# Wacky_Racer_Schematic.net
KiCad netlist of a schematic drawn in Altium Designer
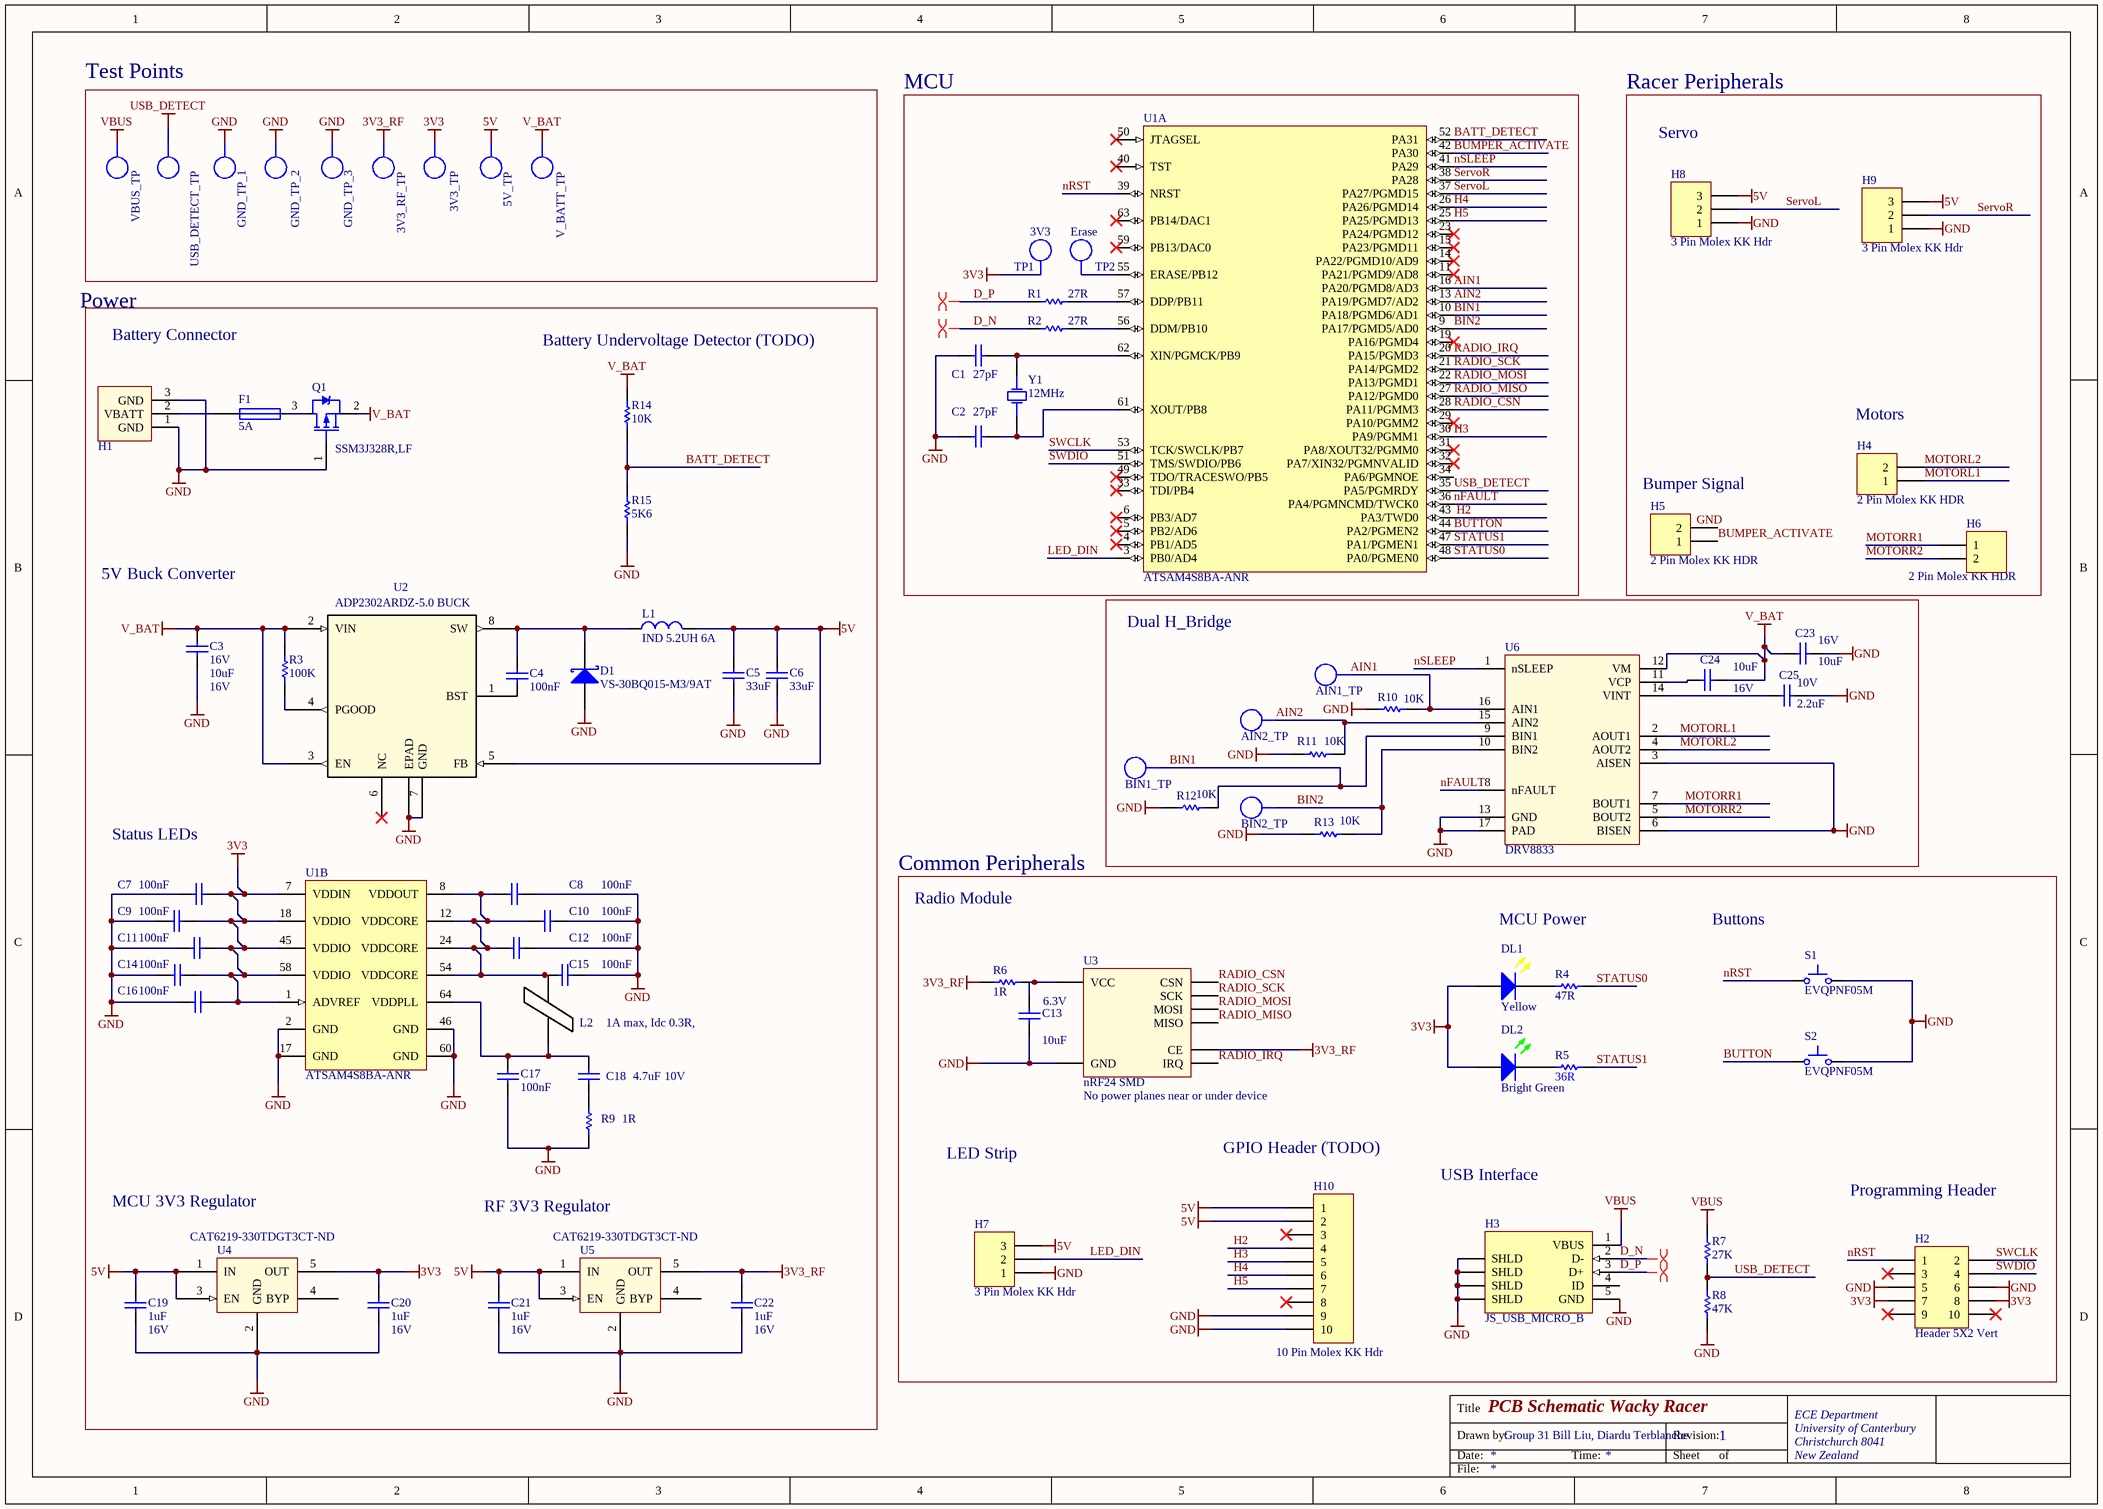
[diagram p0: Wacky Racer Schematic.schdoc]

(export (version "E")
  (design (tool "Eeschema 10.0.6"))
  (components
    (comp (ref "3V3_RF_TP")
      (value "TP")
      (footprint "TP_1206")
      (description "Test-Point 3.3x1.6x2.1mm SMD")
      (fields
        (field (name "MANUFACTURER") "Harwin Inc")
        (field (name "MANUFACTURER PART NUMBER") "S1751-46R")
      )
      (libsource (lib "ECE AD19Components_19V1") (part "TP_1206"))
    )
    (comp (ref "3V3_TP")
      (value "TP")
      (footprint "TP_1206")
      (description "Test-Point 3.3x1.6x2.1mm SMD")
      (fields
        (field (name "MANUFACTURER") "Harwin Inc")
        (field (name "MANUFACTURER PART NUMBER") "S1751-46R")
      )
      (libsource (lib "ECE AD19Components_19V1") (part "TP_1206"))
    )
    (comp (ref "5V_TP")
      (value "TP")
      (footprint "TP_1206")
      (description "Test-Point 3.3x1.6x2.1mm SMD")
      (fields
        (field (name "MANUFACTURER") "Harwin Inc")
        (field (name "MANUFACTURER PART NUMBER") "S1751-46R")
      )
      (libsource (lib "ECE AD19Components_19V1") (part "TP_1206"))
    )
    (comp (ref "AIN1_TP")
      (value "TP")
      (footprint "TP_1206")
      (description "Test-Point 3.3x1.6x2.1mm SMD")
      (fields
        (field (name "MANUFACTURER") "Harwin Inc")
        (field (name "MANUFACTURER PART NUMBER") "S1751-46R")
      )
      (libsource (lib "ECE AD19Components_19V1") (part "TP_1206"))
    )
    (comp (ref "AIN2_TP")
      (value "TP")
      (footprint "TP_1206")
      (description "Test-Point 3.3x1.6x2.1mm SMD")
      (fields
        (field (name "MANUFACTURER") "Harwin Inc")
        (field (name "MANUFACTURER PART NUMBER") "S1751-46R")
      )
      (libsource (lib "ECE AD19Components_19V1") (part "TP_1206"))
    )
    (comp (ref "BIN1_TP")
      (value "TP")
      (footprint "TP_1206")
      (description "Test-Point 3.3x1.6x2.1mm SMD")
      (fields
        (field (name "MANUFACTURER") "Harwin Inc")
        (field (name "MANUFACTURER PART NUMBER") "S1751-46R")
      )
      (libsource (lib "ECE AD19Components_19V1") (part "TP_1206"))
    )
    (comp (ref "BIN2_TP")
      (value "TP")
      (footprint "TP_1206")
      (description "Test-Point 3.3x1.6x2.1mm SMD")
      (fields
        (field (name "MANUFACTURER") "Harwin Inc")
        (field (name "MANUFACTURER PART NUMBER") "S1751-46R")
      )
      (libsource (lib "ECE AD19Components_19V1") (part "TP_1206"))
    )
    (comp (ref "C1")
      (value "27pF")
      (footprint "CAPC1608L")
      (description "CAP CER 27pF NPO/COG +-5% 50V 0603")
      (libsource (lib "ECE AD19Components_19V1") (part "CC_27pF_0603"))
    )
    (comp (ref "C2")
      (value "27pF")
      (footprint "CAPC1608L")
      (description "CAP CER 27pF NPO/COG +-5% 50V 0603")
      (libsource (lib "ECE AD19Components_19V1") (part "CC_27pF_0603"))
    )
    (comp (ref "C3")
      (value "10uF")
      (footprint "CAPC2012L")
      (description "CAP CER 10uF X5R 16V 0805")
      (fields
        (field (name "MANUFACTURER") "Samsung Electro-Mechanics")
        (field (name "MANUFACTURER PART NUMBER") "CL21A106KOQNNWE")
        (field (name "VOLTAGE - RATED") "16V")
        (field (name "MAX VOLTAGE") "16V")
      )
      (libsource (lib "ENCE461AD19_19V2") (part "CC_10uF_16V_0805"))
    )
    (comp (ref "C4")
      (value "100nF")
      (footprint "CAPC1608L")
      (description "CAP CER 100nF X7R +-10% 50V 0603")
      (libsource (lib "ECE AD19Components_19V1") (part "CC_100nF_0603"))
    )
    (comp (ref "C5")
      (value "33uF")
      (footprint "CAPC2012L")
      (description "CAP CER 33uF X5R 6V3 0805")
      (fields
        (field (name "MANUFACTURER") "TDK Corporation")
        (field (name "MANUFACTURER PART NUMBER") "C2012X5R0J336M125AC")
      )
      (libsource (lib "ENCE461AD19_19V2") (part "CC_33uF_6V3_0805"))
    )
    (comp (ref "C6")
      (value "33uF")
      (footprint "CAPC2012L")
      (description "CAP CER 33uF X5R 6V3 0805")
      (fields
        (field (name "MANUFACTURER") "TDK Corporation")
        (field (name "MANUFACTURER PART NUMBER") "C2012X5R0J336M125AC")
      )
      (libsource (lib "ENCE461AD19_19V2") (part "CC_33uF_6V3_0805"))
    )
    (comp (ref "C7")
      (value "100nF")
      (footprint "CAPC1608L")
      (description "CAP CER 100nF X7R +-10% 50V 0603")
      (libsource (lib "ECE AD19Components_19V1") (part "CC_100nF_0603"))
    )
    (comp (ref "C8")
      (value "100nF")
      (footprint "CAPC1608L")
      (description "CAP CER 100nF X7R +-10% 50V 0603")
      (libsource (lib "ECE AD19Components_19V1") (part "CC_100nF_0603"))
    )
    (comp (ref "C9")
      (value "100nF")
      (footprint "CAPC1608L")
      (description "CAP CER 100nF X7R +-10% 50V 0603")
      (libsource (lib "ECE AD19Components_19V1") (part "CC_100nF_0603"))
    )
    (comp (ref "C10")
      (value "100nF")
      (footprint "CAPC1608L")
      (description "CAP CER 100nF X7R +-10% 50V 0603")
      (libsource (lib "ECE AD19Components_19V1") (part "CC_100nF_0603"))
    )
    (comp (ref "C11")
      (value "100nF")
      (footprint "CAPC1608L")
      (description "CAP CER 100nF X7R +-10% 50V 0603")
      (libsource (lib "ECE AD19Components_19V1") (part "CC_100nF_0603"))
    )
    (comp (ref "C12")
      (value "100nF")
      (footprint "CAPC1608L")
      (description "CAP CER 100nF X7R +-10% 50V 0603")
      (libsource (lib "ECE AD19Components_19V1") (part "CC_100nF_0603"))
    )
    (comp (ref "C13")
      (value "10uF")
      (footprint "CAPC1608L")
      (description "CAP CER 10UF X5R +-20% 6V3 0603")
      (fields (field (name "VOLTAGE - RATED") "6.3V"))
      (libsource (lib "ECE AD19Components_19V1") (part "CC_10uF_0603"))
    )
    (comp (ref "C14")
      (value "100nF")
      (footprint "CAPC1608L")
      (description "CAP CER 100nF X7R +-10% 50V 0603")
      (libsource (lib "ECE AD19Components_19V1") (part "CC_100nF_0603"))
    )
    (comp (ref "C15")
      (value "100nF")
      (footprint "CAPC1608L")
      (description "CAP CER 100nF X7R +-10% 50V 0603")
      (libsource (lib "ECE AD19Components_19V1") (part "CC_100nF_0603"))
    )
    (comp (ref "C16")
      (value "100nF")
      (footprint "CAPC1608L")
      (description "CAP CER 100nF X7R +-10% 50V 0603")
      (libsource (lib "ECE AD19Components_19V1") (part "CC_100nF_0603"))
    )
    (comp (ref "C17")
      (value "100nF")
      (footprint "CAPC1608L")
      (description "CAP CER 100nF X7R +-10% 50V 0603")
      (libsource (lib "ECE AD19Components_19V1") (part "CC_100nF_0603"))
    )
    (comp (ref "C18")
      (value "4.7uF")
      (footprint "CAPC1608N")
      (description "CAP CER 4.7uF X5R +-20%  10V 0603")
      (fields (field (name "MAX VOLTAGE") "10V"))
      (libsource (lib "ECE AD19Components_19V1") (part "CC_4.7uF_0603"))
    )
    (comp (ref "C19")
      (value "1uF")
      (footprint "CAPC1608L")
      (description "CAP CER 1uF Y5V -20% +80% 16V 0603")
      (fields (field (name "MAX VOLTAGE") "16V"))
      (libsource (lib "ECE AD19Components_19V1") (part "CC_1uF_0603"))
    )
    (comp (ref "C20")
      (value "1uF")
      (footprint "CAPC1608L")
      (description "CAP CER 1uF Y5V -20% +80% 16V 0603")
      (fields (field (name "MAX VOLTAGE") "16V"))
      (libsource (lib "ECE AD19Components_19V1") (part "CC_1uF_0603"))
    )
    (comp (ref "C21")
      (value "1uF")
      (footprint "CAPC1608L")
      (description "CAP CER 1uF Y5V -20% +80% 16V 0603")
      (fields (field (name "MAX VOLTAGE") "16V"))
      (libsource (lib "ECE AD19Components_19V1") (part "CC_1uF_0603"))
    )
    (comp (ref "C22")
      (value "1uF")
      (footprint "CAPC1608L")
      (description "CAP CER 1uF Y5V -20% +80% 16V 0603")
      (fields (field (name "MAX VOLTAGE") "16V"))
      (libsource (lib "ECE AD19Components_19V1") (part "CC_1uF_0603"))
    )
    (comp (ref "C23")
      (value "10uF")
      (footprint "CAPC2012L")
      (description "CAP CER 10uF X5R 16V 0805")
      (fields
        (field (name "MANUFACTURER") "Samsung Electro-Mechanics")
        (field (name "MANUFACTURER PART NUMBER") "CL21A106KOQNNWE")
        (field (name "VOLTAGE - RATED") "16V")
      )
      (libsource (lib "ENCE461AD19_19V2") (part "CC_10uF_16V_0805"))
    )
    (comp (ref "C24")
      (value "10uF")
      (footprint "CAPC2012L")
      (description "CAP CER 10uF X5R 16V 0805")
      (fields
        (field (name "MANUFACTURER") "Samsung Electro-Mechanics")
        (field (name "MANUFACTURER PART NUMBER") "CL21A106KOQNNWE")
        (field (name "VOLTAGE - RATED") "16V")
      )
      (libsource (lib "ENCE461AD19_19V2") (part "CC_10uF_16V_0805"))
    )
    (comp (ref "C25")
      (value "2.2uF")
      (footprint "CAPC1608L")
      (description "CAP CER 2.2uF X5R +-20% 10V 0603")
      (fields (field (name "MAX VOLTAGE") "10V"))
      (libsource (lib "ECE AD19Components_19V1") (part "CC_2.2uF_0603"))
    )
    (comp (ref "D1")
      (value "VS-30BQ015-M3/9AT")
      (footprint "SMC")
      (description "DIODE, SCHOTTKY, 3A, 15V, DO-214AB / SMC")
      (fields (field (name "MANUFACTURER") "Vishay Semiconductors"))
      (libsource (lib "ECE AD19Components_19V1") (part "DS_VS-30BQ015-M3"))
    )
    (comp (ref "DL1")
      (value "Yellow")
      (footprint "WL-SMCW0603")
      (description "LED Yellow 120mcd 0603 SMD")
      (fields
        (field (name "MANUFACTURER") "WURTH ELEKTRONIK")
        (field (name "MANUFACTURER PART NUMBER") "150060YS75000")
        (field (name "LED COLOUR") "Yellow")
      )
      (libsource (lib "ECE AD19Components_19V1") (part "DL_150060YS75000"))
    )
    (comp (ref "DL2")
      (value "Bright Green")
      (footprint "WL-SMCW0603")
      (description "LED Bright Green 40mcd 0603 SMD")
      (fields
        (field (name "MANUFACTURER") "WURTH ELEKTRONIK")
        (field (name "MANUFACTURER PART NUMBER") "150060VS75000")
        (field (name "LED COLOUR") "Bright Green")
      )
      (libsource (lib "ECE AD19Components_19V1") (part "DL_150060VS75000"))
    )
    (comp (ref "F1")
      (value "5A")
      (footprint "RESC3216N")
      (description "Fuse 5.0A Fast Acting 1206 SMD")
      (fields (field (name "MANUFACTURER PART NUMBER") "C1F5") (field (name "MANUFACTURER") "Bel TRP"))
      (libsource (lib "ECE AD19Components_19V1") (part "FS_Fuse_5.0A"))
    )
    (comp (ref "GND_TP_1")
      (value "TP")
      (footprint "TP_1206")
      (description "Test-Point 3.3x1.6x2.1mm SMD")
      (fields
        (field (name "MANUFACTURER") "Harwin Inc")
        (field (name "MANUFACTURER PART NUMBER") "S1751-46R")
      )
      (libsource (lib "ECE AD19Components_19V1") (part "TP_1206"))
    )
    (comp (ref "GND_TP_2")
      (value "TP")
      (footprint "TP_1206")
      (description "Test-Point 3.3x1.6x2.1mm SMD")
      (fields
        (field (name "MANUFACTURER") "Harwin Inc")
        (field (name "MANUFACTURER PART NUMBER") "S1751-46R")
      )
      (libsource (lib "ECE AD19Components_19V1") (part "TP_1206"))
    )
    (comp (ref "GND_TP_3")
      (value "TP")
      (footprint "TP_1206")
      (description "Test-Point 3.3x1.6x2.1mm SMD")
      (fields
        (field (name "MANUFACTURER") "Harwin Inc")
        (field (name "MANUFACTURER PART NUMBER") "S1751-46R")
      )
      (libsource (lib "ECE AD19Components_19V1") (part "TP_1206"))
    )
    (comp (ref "H1")
      (value "Battery_HEADER_3pin")
      (footprint "BATT_HEADER_3POS")
      (description "3Pin Header 2.54mm spacing")
      (libsource (lib "ENCE461AD19_19V2") (part "Battery_HEADER_3pin"))
    )
    (comp (ref "H2")
      (value "Header 5X2 Vert")
      (footprint "IDC2.54-V10D")
      (description "IDC Header, 2,54mm, 10-Pin, Vert")
      (libsource (lib "ECE AD19Components_19V1") (part "JA_HDR_IDC_5X2_VERT"))
    )
    (comp (ref "H3")
      (value "JS_USB_MICRO_B")
      (footprint "FCI_USB_10118194-0001LF")
      (description "CONN USB MICRO B RECPT SMT R/A")
      (fields (field (name "MANUFACTURER") "FCI") (field (name "MANUFACTURER PART NUMBER") "10118194-0001LF"))
      (libsource (lib "ECE AD19Components_19V1") (part "JS_USB_MICRO_B_SMT"))
    )
    (comp (ref "H4")
      (value "2 Pin Molex KK HDR")
      (footprint "MOLEX_KK_2_HDR")
      (description "CONN HEADER 2POS 2.54mm VERT_Thru Hole")
      (libsource (lib "ECE AD19Components_19V1") (part "JA_MOLEX_KK_2POS"))
    )
    (comp (ref "H5")
      (value "2 Pin Molex KK HDR")
      (footprint "MOLEX_KK_2_HDR")
      (description "CONN HEADER 2POS 2.54mm VERT_Thru Hole")
      (libsource (lib "ECE AD19Components_19V1") (part "JA_MOLEX_KK_2POS"))
    )
    (comp (ref "H6")
      (value "2 Pin Molex KK HDR")
      (footprint "MOLEX_KK_2_HDR")
      (description "CONN HEADER 2POS 2.54mm VERT_Thru Hole")
      (libsource (lib "") (part "JA_MOLEX_KK_2POS_1"))
    )
    (comp (ref "H7")
      (value "3 Pin Molex KK Hdr")
      (footprint "MOLEX_KK_3_HDR")
      (description "CONN HEADER 3POS 2.54mm VERT_Thru Hole")
      (fields (field (name "MANUFACTURER") "Molex"))
      (libsource (lib "ECE AD19Components_19V1") (part "JA_MOLEX_KK_3POS"))
    )
    (comp (ref "H8")
      (value "3 Pin Molex KK Hdr")
      (footprint "MOLEX_KK_3_HDR")
      (description "CONN HEADER 3POS 2.54mm VERT_Thru Hole")
      (fields (field (name "MANUFACTURER") "Molex"))
      (libsource (lib "ECE AD19Components_19V1") (part "JA_MOLEX_KK_3POS"))
    )
    (comp (ref "H9")
      (value "3 Pin Molex KK Hdr")
      (footprint "MOLEX_KK_3_HDR")
      (description "CONN HEADER 3POS 2.54mm VERT_Thru Hole")
      (fields (field (name "MANUFACTURER") "Molex"))
      (libsource (lib "ECE AD19Components_19V1") (part "JA_MOLEX_KK_3POS"))
    )
    (comp (ref "H10")
      (value "10 Pin Molex KK Hdr")
      (footprint "MOLEX_KK_10_HDR")
      (description "CONN HEADER 10POS 2.54mm VERT_ Thru Hole")
      (libsource (lib "ECE AD19Components_19V1") (part "JA_MOLEX_KK_10POS"))
    )
    (comp (ref "L1")
      (value "IND 5.2UH 6A")
      (footprint "INDUCTOR5u2")
      (description "FIXED IND 5.2UH 6A 22 MOHM SMD")
      (fields
        (field (name "MANUFACTURER") "Sumida America Components Inc.")
        (field (name "MANUFACTURER PART NUMBER") "CDRH104RNP-5R2NC")
      )
      (libsource (lib "ENCE461AD19_19V2") (part "CDRH104RNP-5R2NC"))
    )
    (comp (ref "L2")
      (value "1A max, Idc 0.3R,")
      (footprint "INDC3216L")
      (description "Ferrite Bead, Rdc 0.3R, Z100MHZ 600R, Imax 1A, SMD 1206")
      (fields
        (field (name "MANUFACTURER") "FAIR-RITE")
        (field (name "MANUFACTURER PART NUMBER") "2512066017Y1")
      )
      (libsource (lib "ECE AD19Components_19V1") (part "IN_Ferrite-Bead"))
    )
    (comp (ref "Q1")
      (value "SSM3J328R,LF")
      (footprint "SOT23_L")
      (description "MOSFET P-CH 20V 6A SOT23-3")
      (fields
        (field (name "MANUFACTURER") "Toshiba")
        (field (name "MANUFACTURER PART NUMBER") "SSM3J328R,LF")
      )
      (libsource (lib "ECE AD19Components_19V1") (part "TM_SSM3J328R"))
    )
    (comp (ref "R1")
      (value "27R")
      (footprint "RESC1608L")
      (description "RES 27 OHM 1/10W 5% 0603 SMD")
      (libsource (lib "ECE AD19Components_19V1") (part "RS_27R"))
    )
    (comp (ref "R2")
      (value "27R")
      (footprint "RESC1608L")
      (description "RES 27 OHM 1/10W 5% 0603 SMD")
      (libsource (lib "ECE AD19Components_19V1") (part "RS_27R"))
    )
    (comp (ref "R3")
      (value "100K")
      (footprint "RESC1608L")
      (description "RES 100K OHM 1/10W 5% 0603 SMD")
      (libsource (lib "ECE AD19Components_19V1") (part "RS_100K"))
    )
    (comp (ref "R4")
      (value "47R")
      (footprint "RESC1608L")
      (description "RES 47 OHM 1/10W 5% 0603 SMD")
      (libsource (lib "ECE AD19Components_19V1") (part "RS_47R"))
    )
    (comp (ref "R5")
      (value "36R")
      (footprint "RESC1608L")
      (description "RES 36 OHM 1/10W 5% 0603 SMD")
      (libsource (lib "ECE AD19Components_19V1") (part "RS_36R"))
    )
    (comp (ref "R6")
      (value "1R")
      (footprint "RESC3216L")
      (description "RES 1R OHM 1/4W 5% 1206 SMD")
      (libsource (lib "ECE AD19Components_19V1") (part "RT_1R"))
    )
    (comp (ref "R7")
      (value "27K")
      (footprint "RESC1608L")
      (description "RES 27K OHM 1/10W 5% 0603 SMD")
      (libsource (lib "ECE AD19Components_19V1") (part "RS_27K"))
    )
    (comp (ref "R8")
      (value "47K")
      (footprint "RESC1608N")
      (description "RES 47.0K OHM 1/10W 5% 0603 SMD")
      (libsource (lib "ECE AD19Components_19V1") (part "RS_47K"))
    )
    (comp (ref "R9")
      (value "1R")
      (footprint "RESC3216L")
      (description "RES 1R OHM 1/4W 5% 1206 SMD")
      (libsource (lib "ECE AD19Components_19V1") (part "RT_1R"))
    )
    (comp (ref "R10")
      (value "10K")
      (footprint "RESC1608L")
      (description "RES 10.0K OHM 1/10W 5% 0603 SMD")
      (libsource (lib "ECE AD19Components_19V1") (part "RS_10K"))
    )
    (comp (ref "R11")
      (value "10K")
      (footprint "RESC1608L")
      (description "RES 10.0K OHM 1/10W 5% 0603 SMD")
      (libsource (lib "ECE AD19Components_19V1") (part "RS_10K"))
    )
    (comp (ref "R12")
      (value "10K")
      (footprint "RESC1608L")
      (description "RES 10.0K OHM 1/10W 5% 0603 SMD")
      (libsource (lib "ECE AD19Components_19V1") (part "RS_10K"))
    )
    (comp (ref "R13")
      (value "10K")
      (footprint "RESC1608L")
      (description "RES 10.0K OHM 1/10W 5% 0603 SMD")
      (libsource (lib "ECE AD19Components_19V1") (part "RS_10K"))
    )
    (comp (ref "R14")
      (value "10K")
      (footprint "RESC1608L")
      (description "RES 10.0K OHM 1/10W 5% 0603 SMD")
      (libsource (lib "ECE AD19Components_19V1") (part "RS_10K"))
    )
    (comp (ref "R15")
      (value "5K6")
      (footprint "RESC1608L")
      (description "RES 5.6K OHM 1/10W 5% 0603 SMD")
      (libsource (lib "ECE AD19Components_19V1") (part "RS_5K6"))
    )
    (comp (ref "S1")
      (value "EVQPNF05M")
      (footprint "EVQPNF05M")
      (description "Panasonic 6 x 3.5mm SMD Light Touch Switch Type SMD")
      (fields (field (name "MANUFACTURER") "Panasonic"))
      (libsource (lib "ECE AD19Components_19V1") (part "WS_EVQPNF05M"))
    )
    (comp (ref "S2")
      (value "EVQPNF05M")
      (footprint "EVQPNF05M")
      (description "Panasonic 6 x 3.5mm SMD Light Touch Switch Type SMD")
      (fields (field (name "MANUFACTURER") "Panasonic"))
      (libsource (lib "ECE AD19Components_19V1") (part "WS_EVQPNF05M"))
    )
    (comp (ref "TP1")
      (value "3V3")
      (footprint "TP_1206")
      (description "Test-Point 3.3x1.6x2.1mm SMD")
      (fields
        (field (name "MANUFACTURER") "Harwin Inc")
        (field (name "MANUFACTURER PART NUMBER") "S1751-46R")
      )
      (libsource (lib "ECE AD19Components_19V1") (part "TP_1206"))
    )
    (comp (ref "TP2")
      (value "Erase")
      (footprint "TP_1206")
      (description "Test-Point 3.3x1.6x2.1mm SMD")
      (fields
        (field (name "MANUFACTURER") "Harwin Inc")
        (field (name "MANUFACTURER PART NUMBER") "S1751-46R")
      )
      (libsource (lib "ECE AD19Components_19V1") (part "TP_1206"))
    )
    (comp (ref "U1")
      (value "ATSAM4S8BA-ANR")
      (footprint "LQFP64_L")
      (description "IC MCU 32BIT 512KB FLASH 64LQFP")
      (fields (field (name "MANUFACTURER") "Atmel"))
      (libsource (lib "ECE AD19Components_19V1") (part "SE_ATSAM4S16BA-MU"))
    )
    (comp (ref "U2")
      (value "ADP2302ARDZ-5.0 BUCK")
      (footprint "RD_8_1")
      (description "IC REG BUCK 5V 2A 8SOIC")
      (fields (field (name "MANUFACTURER_PART_NUMBER") "ADP2302ARDZ-5.0-R7"))
      (libsource (lib "ENCE461AD19_19V2") (part "ADP2302ARDZ-5.0-R7"))
    )
    (comp (ref "U3")
      (value "nRF24 SMD")
      (footprint "NRF24")
      (description "nRF24 SMD Module")
      (fields (field (name "WARNING") "No power planes near or under device"))
      (libsource (lib "ENCE461AD19_19V2") (part "NRF24"))
    )
    (comp (ref "U4")
      (value "CAT6219-330TDGT3")
      (footprint "SOT95P280X145-5N")
      (description "IC REG LIN 3.3V 500MA TSOT23-5")
      (fields
        (field (name "BASE PART NUMBER") "CAT6219")
        (field (name "SUPPLIER PART NUMBER") "CAT6219-330TDGT3CT-ND")
      )
      (libsource (lib "ENCE461AD19_19V2") (part "SV_CAT6219-330TDGT3"))
    )
    (comp (ref "U5")
      (value "CAT6219-330TDGT3")
      (footprint "SOT95P280X145-5N")
      (description "IC REG LIN 3.3V 500MA TSOT23-5")
      (fields
        (field (name "BASE PART NUMBER") "CAT6219")
        (field (name "SUPPLIER PART NUMBER") "CAT6219-330TDGT3CT-ND")
      )
      (libsource (lib "ENCE461AD19_19V2") (part "SV_CAT6219-330TDGT3"))
    )
    (comp (ref "U6")
      (value "DRV8833")
      (footprint "HTSOP16")
      (description "Dual H-Bridge Motor Driver 1.5A")
      (libsource (lib "ENCE461AD19_19V2") (part "DRV8833"))
    )
    (comp (ref "USB_DETECT_TP")
      (value "TP")
      (footprint "TP_1206")
      (description "Test-Point 3.3x1.6x2.1mm SMD")
      (fields
        (field (name "MANUFACTURER") "Harwin Inc")
        (field (name "MANUFACTURER PART NUMBER") "S1751-46R")
      )
      (libsource (lib "ECE AD19Components_19V1") (part "TP_1206"))
    )
    (comp (ref "VBUS_TP")
      (value "TP")
      (footprint "TP_1206")
      (description "Test-Point 3.3x1.6x2.1mm SMD")
      (fields
        (field (name "MANUFACTURER") "Harwin Inc")
        (field (name "MANUFACTURER PART NUMBER") "S1751-46R")
      )
      (libsource (lib "ECE AD19Components_19V1") (part "TP_1206"))
    )
    (comp (ref "V_BATT_TP")
      (value "TP")
      (footprint "TP_1206")
      (description "Test-Point 3.3x1.6x2.1mm SMD")
      (fields
        (field (name "MANUFACTURER") "Harwin Inc")
        (field (name "MANUFACTURER PART NUMBER") "S1751-46R")
      )
      (libsource (lib "ECE AD19Components_19V1") (part "TP_1206"))
    )
    (comp (ref "Y1")
      (value "12MHz")
      (footprint "6.0X3.5-4")
      (description "CRYSTAL 12MHZ 18PF 6X3.5mm SMD")
      (fields
        (field (name "MANUFACTURER") "CTS-Frequency Controls")
        (field (name "MANUFACTURER PART NUMBER") "406C35D12M00000")
        (field (name "FREQUENCY") "12MHz")
      )
      (libsource (lib "ECE AD19Components_19V1") (part "XT_CRYSTAL_12MHz_18pF"))
    )
  )
  (nets
    (net (code "1") (name "/AIN1") (class "Default")
      (node (ref "AIN1_TP") (pin "1") (pinfunction "1_1") (pintype "passive"))
      (node (ref "R10") (pin "2") (pinfunction "2_2") (pintype "passive"))
      (node (ref "U1") (pin "16") (pinfunction "PA20/PGMD8/AD3_16") (pintype "bidirectional"))
      (node (ref "U6") (pin "16") (pinfunction "AIN1_16") (pintype "passive"))
    )
    (net (code "2") (name "/AIN2") (class "Default")
      (node (ref "AIN2_TP") (pin "1") (pinfunction "1_1") (pintype "passive"))
      (node (ref "R11") (pin "2") (pinfunction "2_2") (pintype "passive"))
      (node (ref "U1") (pin "13") (pinfunction "PA19/PGMD7/AD2_13") (pintype "bidirectional"))
      (node (ref "U6") (pin "15") (pinfunction "AIN2_15") (pintype "passive"))
    )
    (net (code "3") (name "/BATT_DETECT") (class "Default")
      (node (ref "R14") (pin "1") (pinfunction "1_1") (pintype "passive"))
      (node (ref "R15") (pin "2") (pinfunction "2_2") (pintype "passive"))
      (node (ref "U1") (pin "52") (pinfunction "PA31_52") (pintype "bidirectional"))
    )
    (net (code "4") (name "/BIN1") (class "Default")
      (node (ref "BIN1_TP") (pin "1") (pinfunction "1_1") (pintype "passive"))
      (node (ref "R12") (pin "2") (pinfunction "2_2") (pintype "passive"))
      (node (ref "U1") (pin "10") (pinfunction "PA18/PGMD6/AD1_10") (pintype "bidirectional"))
      (node (ref "U6") (pin "9") (pinfunction "BIN1_9") (pintype "passive"))
    )
    (net (code "5") (name "/BIN2") (class "Default")
      (node (ref "BIN2_TP") (pin "1") (pinfunction "1_1") (pintype "passive"))
      (node (ref "R13") (pin "2") (pinfunction "2_2") (pintype "passive"))
      (node (ref "U1") (pin "9") (pinfunction "PA17/PGMD5/AD0_9") (pintype "bidirectional"))
      (node (ref "U6") (pin "10") (pinfunction "BIN2_10") (pintype "passive"))
    )
    (net (code "6") (name "/BUMPER_ACTIVATE") (class "Default")
      (node (ref "H5") (pin "1") (pinfunction "1_1") (pintype "passive"))
      (node (ref "U1") (pin "42") (pinfunction "PA30_42") (pintype "bidirectional"))
    )
    (net (code "7") (name "/BUTTON") (class "Default")
      (node (ref "S2") (pin "1") (pintype "passive"))
      (node (ref "U1") (pin "44") (pinfunction "PA2/PGMEN2_44") (pintype "bidirectional"))
    )
    (net (code "8") (name "/D_N") (class "Default")
      (node (ref "H3") (pin "2") (pinfunction "D-_2") (pintype "input"))
      (node (ref "R2") (pin "1") (pinfunction "1_1") (pintype "passive"))
    )
    (net (code "9") (name "/D_P") (class "Default")
      (node (ref "H3") (pin "3") (pinfunction "D+_3") (pintype "input"))
      (node (ref "R1") (pin "1") (pinfunction "1_1") (pintype "passive"))
    )
    (net (code "10") (name "/H2") (class "Default")
      (node (ref "H10") (pin "4") (pinfunction "4_4") (pintype "passive"))
      (node (ref "U1") (pin "43") (pinfunction "PA3/TWD0_43") (pintype "bidirectional"))
    )
    (net (code "11") (name "/H3") (class "Default")
      (node (ref "H10") (pin "5") (pinfunction "5_5") (pintype "passive"))
      (node (ref "U1") (pin "30") (pinfunction "PA9/PGMM1_30") (pintype "bidirectional"))
    )
    (net (code "12") (name "/H4") (class "Default")
      (node (ref "H10") (pin "6") (pinfunction "6_6") (pintype "passive"))
      (node (ref "U1") (pin "26") (pinfunction "PA26/PGMD14_26") (pintype "bidirectional"))
    )
    (net (code "13") (name "/H5") (class "Default")
      (node (ref "H10") (pin "7") (pinfunction "7_7") (pintype "passive"))
      (node (ref "U1") (pin "25") (pinfunction "PA25/PGMD13_25") (pintype "bidirectional"))
    )
    (net (code "14") (name "/LED_DIN") (class "Default")
      (node (ref "H7") (pin "2") (pinfunction "2_2") (pintype "passive"))
      (node (ref "U1") (pin "3") (pinfunction "PB0/AD4_3") (pintype "bidirectional"))
    )
    (net (code "15") (name "/MOTORL1") (class "Default")
      (node (ref "H4") (pin "1") (pinfunction "1_1") (pintype "passive"))
      (node (ref "U6") (pin "2") (pinfunction "AOUT1_2") (pintype "passive"))
    )
    (net (code "16") (name "/MOTORL2") (class "Default")
      (node (ref "H4") (pin "2") (pinfunction "2_2") (pintype "passive"))
      (node (ref "U6") (pin "4") (pinfunction "AOUT2_4") (pintype "passive"))
    )
    (net (code "17") (name "/MOTORR1") (class "Default")
      (node (ref "H6") (pin "1") (pinfunction "1_1") (pintype "passive"))
      (node (ref "U6") (pin "7") (pinfunction "BOUT1_7") (pintype "passive"))
    )
    (net (code "18") (name "/MOTORR2") (class "Default")
      (node (ref "H6") (pin "2") (pinfunction "2_2") (pintype "passive"))
      (node (ref "U6") (pin "5") (pinfunction "BOUT2_5") (pintype "passive"))
    )
    (net (code "19") (name "/RADIO_CSN") (class "Default")
      (node (ref "U1") (pin "28") (pinfunction "PA11/PGMM3_28") (pintype "bidirectional"))
      (node (ref "U3") (pin "4") (pinfunction "CSN_4") (pintype "passive"))
    )
    (net (code "20") (name "/RADIO_IRQ") (class "Default")
      (node (ref "U1") (pin "20") (pinfunction "PA15/PGMD3_20") (pintype "bidirectional"))
      (node (ref "U3") (pin "8") (pinfunction "IRQ_8") (pintype "passive"))
    )
    (net (code "21") (name "/RADIO_MISO") (class "Default")
      (node (ref "U1") (pin "27") (pinfunction "PA12/PGMD0_27") (pintype "bidirectional"))
      (node (ref "U3") (pin "7") (pinfunction "MISO_7") (pintype "passive"))
    )
    (net (code "22") (name "/RADIO_MOSI") (class "Default")
      (node (ref "U1") (pin "22") (pinfunction "PA13/PGMD1_22") (pintype "bidirectional"))
      (node (ref "U3") (pin "6") (pinfunction "MOSI_6") (pintype "passive"))
    )
    (net (code "23") (name "/RADIO_SCK") (class "Default")
      (node (ref "U1") (pin "21") (pinfunction "PA14/PGMD2_21") (pintype "bidirectional"))
      (node (ref "U3") (pin "5") (pinfunction "SCK_5") (pintype "passive"))
    )
    (net (code "24") (name "/STATUS0") (class "Default")
      (node (ref "R4") (pin "2") (pinfunction "2_2") (pintype "passive"))
      (node (ref "U1") (pin "48") (pinfunction "PA0/PGMEN0_48") (pintype "bidirectional"))
    )
    (net (code "25") (name "/STATUS1") (class "Default")
      (node (ref "R5") (pin "2") (pinfunction "2_2") (pintype "passive"))
      (node (ref "U1") (pin "47") (pinfunction "PA1/PGMEN1_47") (pintype "bidirectional"))
    )
    (net (code "26") (name "/SWCLK") (class "Default")
      (node (ref "H2") (pin "2") (pinfunction "2_2") (pintype "passive"))
      (node (ref "U1") (pin "53") (pinfunction "TCK/SWCLK/PB7_53") (pintype "bidirectional"))
    )
    (net (code "27") (name "/SWDIO") (class "Default")
      (node (ref "H2") (pin "4") (pinfunction "4_4") (pintype "passive"))
      (node (ref "U1") (pin "51") (pinfunction "TMS/SWDIO/PB6_51") (pintype "bidirectional"))
    )
    (net (code "28") (name "/ServoL") (class "Default")
      (node (ref "H8") (pin "2") (pinfunction "2_2") (pintype "passive"))
      (node (ref "U1") (pin "37") (pinfunction "PA27/PGMD15_37") (pintype "bidirectional"))
    )
    (net (code "29") (name "/ServoR") (class "Default")
      (node (ref "H9") (pin "2") (pinfunction "2_2") (pintype "passive"))
      (node (ref "U1") (pin "38") (pinfunction "PA28_38") (pintype "bidirectional"))
    )
    (net (code "30") (name "/nFAULT") (class "Default")
      (node (ref "U1") (pin "36") (pinfunction "PA4/PGMNCMD/TWCK0_36") (pintype "bidirectional"))
      (node (ref "U6") (pin "8") (pinfunction "nFAULT_8") (pintype "passive"))
    )
    (net (code "31") (name "/nRST") (class "Default")
      (node (ref "H2") (pin "1") (pinfunction "1_1") (pintype "passive"))
      (node (ref "S1") (pin "1") (pintype "passive"))
      (node (ref "U1") (pin "39") (pinfunction "NRST_39") (pintype "bidirectional"))
    )
    (net (code "32") (name "/nSLEEP") (class "Default")
      (node (ref "U1") (pin "41") (pinfunction "PA29_41") (pintype "bidirectional"))
      (node (ref "U6") (pin "1") (pinfunction "nSLEEP_1") (pintype "passive"))
    )
    (net (code "33") (name "3V3") (class "Default")
      (node (ref "3V3_TP") (pin "1") (pinfunction "1_1") (pintype "passive"))
      (node (ref "C11") (pin "2") (pinfunction "2_2") (pintype "passive"))
      (node (ref "C14") (pin "2") (pinfunction "2_2") (pintype "passive"))
      (node (ref "C16") (pin "2") (pinfunction "2_2") (pintype "passive"))
      (node (ref "C20") (pin "2") (pinfunction "2_2") (pintype "passive"))
      (node (ref "C7") (pin "2") (pinfunction "2_2") (pintype "passive"))
      (node (ref "C9") (pin "2") (pinfunction "2_2") (pintype "passive"))
      (node (ref "DL1") (pin "2") (pinfunction "A_2") (pintype "passive"))
      (node (ref "DL2") (pin "2") (pinfunction "A_2") (pintype "passive"))
      (node (ref "H2") (pin "7") (pinfunction "7_7") (pintype "passive"))
      (node (ref "H2") (pin "8") (pinfunction "8_8") (pintype "passive"))
      (node (ref "TP1") (pin "1") (pinfunction "1_1") (pintype "passive"))
      (node (ref "U1") (pin "1") (pinfunction "ADVREF_1") (pintype "input"))
      (node (ref "U1") (pin "18") (pinfunction "VDDIO_18") (pintype "power_in"))
      (node (ref "U1") (pin "45") (pinfunction "VDDIO_45") (pintype "power_in"))
      (node (ref "U1") (pin "58") (pinfunction "VDDIO_58") (pintype "power_in"))
      (node (ref "U1") (pin "7") (pinfunction "VDDIN_7") (pintype "power_in"))
      (node (ref "U4") (pin "5") (pinfunction "OUT_5") (pintype "power_in"))
    )
    (net (code "34") (name "3V3_RF") (class "Default")
      (node (ref "3V3_RF_TP") (pin "1") (pinfunction "1_1") (pintype "passive"))
      (node (ref "C22") (pin "2") (pinfunction "2_2") (pintype "passive"))
      (node (ref "R6") (pin "1") (pinfunction "1_1") (pintype "passive"))
      (node (ref "U3") (pin "3") (pinfunction "CE_3") (pintype "passive"))
      (node (ref "U5") (pin "5") (pinfunction "OUT_5") (pintype "power_in"))
    )
    (net (code "35") (name "5V") (class "Default")
      (node (ref "5V_TP") (pin "1") (pinfunction "1_1") (pintype "passive"))
      (node (ref "C19") (pin "2") (pinfunction "2_2") (pintype "passive"))
      (node (ref "C21") (pin "2") (pinfunction "2_2") (pintype "passive"))
      (node (ref "C5") (pin "2") (pinfunction "2_2") (pintype "passive"))
      (node (ref "C6") (pin "2") (pinfunction "2_2") (pintype "passive"))
      (node (ref "H10") (pin "1") (pinfunction "1_1") (pintype "passive"))
      (node (ref "H10") (pin "2") (pinfunction "2_2") (pintype "passive"))
      (node (ref "H7") (pin "3") (pinfunction "3_3") (pintype "passive"))
      (node (ref "H8") (pin "3") (pinfunction "3_3") (pintype "passive"))
      (node (ref "H9") (pin "3") (pinfunction "3_3") (pintype "passive"))
      (node (ref "L1") (pin "2") (pintype "passive"))
      (node (ref "U2") (pin "5") (pinfunction "FB_5") (pintype "input"))
      (node (ref "U4") (pin "1") (pinfunction "IN_1") (pintype "power_in"))
      (node (ref "U4") (pin "3") (pinfunction "EN_3") (pintype "input"))
      (node (ref "U5") (pin "1") (pinfunction "IN_1") (pintype "power_in"))
      (node (ref "U5") (pin "3") (pinfunction "EN_3") (pintype "input"))
    )
    (net (code "36") (name "GND") (class "Default")
      (node (ref "C1") (pin "1") (pinfunction "1_1") (pintype "passive"))
      (node (ref "C10") (pin "2") (pinfunction "2_2") (pintype "passive"))
      (node (ref "C11") (pin "1") (pinfunction "1_1") (pintype "passive"))
      (node (ref "C12") (pin "2") (pinfunction "2_2") (pintype "passive"))
      (node (ref "C13") (pin "1") (pinfunction "1_1") (pintype "passive"))
      (node (ref "C14") (pin "1") (pinfunction "1_1") (pintype "passive"))
      (node (ref "C15") (pin "2") (pinfunction "2_2") (pintype "passive"))
      (node (ref "C16") (pin "1") (pinfunction "1_1") (pintype "passive"))
      (node (ref "C17") (pin "1") (pinfunction "1_1") (pintype "passive"))
      (node (ref "C19") (pin "1") (pinfunction "1_1") (pintype "passive"))
      (node (ref "C2") (pin "1") (pinfunction "1_1") (pintype "passive"))
      (node (ref "C20") (pin "1") (pinfunction "1_1") (pintype "passive"))
      (node (ref "C21") (pin "1") (pinfunction "1_1") (pintype "passive"))
      (node (ref "C22") (pin "1") (pinfunction "1_1") (pintype "passive"))
      (node (ref "C23") (pin "2") (pinfunction "2_2") (pintype "passive"))
      (node (ref "C25") (pin "2") (pinfunction "2_2") (pintype "passive"))
      (node (ref "C3") (pin "1") (pinfunction "1_1") (pintype "passive"))
      (node (ref "C5") (pin "1") (pinfunction "1_1") (pintype "passive"))
      (node (ref "C6") (pin "1") (pinfunction "1_1") (pintype "passive"))
      (node (ref "C7") (pin "1") (pinfunction "1_1") (pintype "passive"))
      (node (ref "C8") (pin "2") (pinfunction "2_2") (pintype "passive"))
      (node (ref "C9") (pin "1") (pinfunction "1_1") (pintype "passive"))
      (node (ref "D1") (pin "1") (pinfunction "A_1") (pintype "passive"))
      (node (ref "GND_TP_1") (pin "1") (pinfunction "1_1") (pintype "passive"))
      (node (ref "GND_TP_2") (pin "1") (pinfunction "1_1") (pintype "passive"))
      (node (ref "GND_TP_3") (pin "1") (pinfunction "1_1") (pintype "passive"))
      (node (ref "H1") (pin "1") (pinfunction "GND_1") (pintype "passive"))
      (node (ref "H1") (pin "3") (pinfunction "GND_3") (pintype "passive"))
      (node (ref "H10") (pin "10") (pinfunction "10_10") (pintype "passive"))
      (node (ref "H10") (pin "9") (pinfunction "9_9") (pintype "passive"))
      (node (ref "H2") (pin "5") (pinfunction "5_5") (pintype "passive"))
      (node (ref "H2") (pin "6") (pinfunction "6_6") (pintype "passive"))
      (node (ref "H3") (pin "5") (pinfunction "GND_5") (pintype "passive"))
      (node (ref "H3") (pin "6") (pinfunction "SHLD_6") (pintype "passive"))
      (node (ref "H7") (pin "1") (pinfunction "1_1") (pintype "passive"))
      (node (ref "H8") (pin "1") (pinfunction "1_1") (pintype "passive"))
      (node (ref "H9") (pin "1") (pinfunction "1_1") (pintype "passive"))
      (node (ref "Q1") (pin "1") (pinfunction "1_1") (pintype "passive"))
      (node (ref "R10") (pin "1") (pinfunction "1_1") (pintype "passive"))
      (node (ref "R11") (pin "1") (pinfunction "1_1") (pintype "passive"))
      (node (ref "R12") (pin "1") (pinfunction "1_1") (pintype "passive"))
      (node (ref "R13") (pin "1") (pinfunction "1_1") (pintype "passive"))
      (node (ref "R15") (pin "1") (pinfunction "1_1") (pintype "passive"))
      (node (ref "R8") (pin "1") (pinfunction "1_1") (pintype "passive"))
      (node (ref "R9") (pin "1") (pinfunction "1_1") (pintype "passive"))
      (node (ref "S1") (pin "2") (pintype "passive"))
      (node (ref "S2") (pin "2") (pintype "passive"))
      (node (ref "U1") (pin "17") (pinfunction "GND_17") (pintype "power_in"))
      (node (ref "U1") (pin "2") (pinfunction "GND_2") (pintype "power_in"))
      (node (ref "U1") (pin "46") (pinfunction "GND_46") (pintype "power_in"))
      (node (ref "U1") (pin "60") (pinfunction "GND_60") (pintype "power_in"))
      (node (ref "U2") (pin "7") (pinfunction "GND_7") (pintype "power_in"))
      (node (ref "U2") (pin "EPAD") (pinfunction "EPAD_EPAD") (pintype "passive"))
      (node (ref "U3") (pin "2") (pinfunction "GND_2") (pintype "passive"))
      (node (ref "U4") (pin "2") (pinfunction "GND_2") (pintype "power_in"))
      (node (ref "U5") (pin "2") (pinfunction "GND_2") (pintype "power_in"))
      (node (ref "U6") (pin "13") (pinfunction "GND_13") (pintype "passive"))
      (node (ref "U6") (pin "17") (pinfunction "PAD_17") (pintype "passive"))
      (node (ref "U6") (pin "3") (pinfunction "AISEN_3") (pintype "passive"))
      (node (ref "U6") (pin "6") (pinfunction "BISEN_6") (pintype "passive"))
    )
    (net (code "37") (name "Net-(C18-Pad1)") (class "Default")
      (node (ref "C18") (pin "1") (pinfunction "1_1") (pintype "passive"))
      (node (ref "R9") (pin "2") (pinfunction "2_2") (pintype "passive"))
    )
    (net (code "38") (name "Net-(D1-K)") (class "Default")
      (node (ref "C4") (pin "2") (pinfunction "2_2") (pintype "passive"))
      (node (ref "D1") (pin "2") (pinfunction "K_2") (pintype "passive"))
      (node (ref "L1") (pin "1") (pintype "passive"))
      (node (ref "U2") (pin "8") (pinfunction "SW_8") (pintype "output"))
    )
    (net (code "39") (name "Net-(DL1-K)") (class "Default")
      (node (ref "DL1") (pin "1") (pinfunction "K_1") (pintype "passive"))
      (node (ref "R4") (pin "1") (pinfunction "1_1") (pintype "passive"))
    )
    (net (code "40") (name "Net-(DL2-K)") (class "Default")
      (node (ref "DL2") (pin "1") (pinfunction "K_1") (pintype "passive"))
      (node (ref "R5") (pin "1") (pinfunction "1_1") (pintype "passive"))
    )
    (net (code "41") (name "Net-(F1-Pad2)") (class "Default")
      (node (ref "F1") (pin "2") (pinfunction "2_2") (pintype "passive"))
      (node (ref "Q1") (pin "3") (pinfunction "3_3") (pintype "passive"))
    )
    (net (code "42") (name "Net-(H1-VBATT)") (class "Default")
      (node (ref "F1") (pin "1") (pinfunction "1_1") (pintype "passive"))
      (node (ref "H1") (pin "2") (pinfunction "VBATT_2") (pintype "passive"))
    )
    (net (code "43") (name "Net-(U1A-DDM{slash}PB10)") (class "Default")
      (node (ref "R2") (pin "2") (pinfunction "2_2") (pintype "passive"))
      (node (ref "U1") (pin "56") (pinfunction "DDM/PB10_56") (pintype "bidirectional"))
    )
    (net (code "44") (name "Net-(U1A-DDP{slash}PB11)") (class "Default")
      (node (ref "R1") (pin "2") (pinfunction "2_2") (pintype "passive"))
      (node (ref "U1") (pin "57") (pinfunction "DDP/PB11_57") (pintype "bidirectional"))
    )
    (net (code "45") (name "Net-(U1A-ERASE{slash}PB12)") (class "Default")
      (node (ref "TP2") (pin "1") (pinfunction "1_1") (pintype "passive"))
      (node (ref "U1") (pin "55") (pinfunction "ERASE/PB12_55") (pintype "bidirectional"))
    )
    (net (code "46") (name "Net-(U1A-XIN{slash}PGMCK{slash}PB9)") (class "Default")
      (node (ref "C1") (pin "2") (pinfunction "2_2") (pintype "passive"))
      (node (ref "U1") (pin "62") (pinfunction "XIN/PGMCK/PB9_62") (pintype "bidirectional"))
      (node (ref "Y1") (pin "1") (pinfunction "OSC1_1") (pintype "passive"))
    )
    (net (code "47") (name "Net-(U1A-XOUT{slash}PB8)") (class "Default")
      (node (ref "C2") (pin "2") (pinfunction "2_2") (pintype "passive"))
      (node (ref "U1") (pin "61") (pinfunction "XOUT/PB8_61") (pintype "bidirectional"))
      (node (ref "Y1") (pin "3") (pinfunction "OSC2_3") (pintype "passive"))
    )
    (net (code "48") (name "Net-(U1B-VDDOUT)") (class "Default")
      (node (ref "C10") (pin "1") (pinfunction "1_1") (pintype "passive"))
      (node (ref "C12") (pin "1") (pinfunction "1_1") (pintype "passive"))
      (node (ref "C15") (pin "1") (pinfunction "1_1") (pintype "passive"))
      (node (ref "C8") (pin "1") (pinfunction "1_1") (pintype "passive"))
      (node (ref "L2") (pin "2") (pinfunction "2_2") (pintype "passive"))
      (node (ref "U1") (pin "12") (pinfunction "VDDCORE_12") (pintype "power_in"))
      (node (ref "U1") (pin "24") (pinfunction "VDDCORE_24") (pintype "power_in"))
      (node (ref "U1") (pin "54") (pinfunction "VDDCORE_54") (pintype "power_in"))
      (node (ref "U1") (pin "8") (pinfunction "VDDOUT_8") (pintype "power_in"))
    )
    (net (code "49") (name "Net-(U1B-VDDPLL)") (class "Default")
      (node (ref "C17") (pin "2") (pinfunction "2_2") (pintype "passive"))
      (node (ref "C18") (pin "2") (pinfunction "2_2") (pintype "passive"))
      (node (ref "L2") (pin "1") (pinfunction "1_1") (pintype "passive"))
      (node (ref "U1") (pin "64") (pinfunction "VDDPLL_64") (pintype "power_in"))
    )
    (net (code "50") (name "Net-(U2-BST)") (class "Default")
      (node (ref "C4") (pin "1") (pinfunction "1_1") (pintype "passive"))
      (node (ref "U2") (pin "1") (pinfunction "BST_1") (pintype "passive"))
    )
    (net (code "51") (name "Net-(U2-PGOOD)") (class "Default")
      (node (ref "R3") (pin "1") (pinfunction "1_1") (pintype "passive"))
      (node (ref "U2") (pin "4") (pinfunction "PGOOD_4") (pintype "output"))
    )
    (net (code "52") (name "Net-(U3-VCC)") (class "Default")
      (node (ref "C13") (pin "2") (pinfunction "2_2") (pintype "passive"))
      (node (ref "R6") (pin "2") (pinfunction "2_2") (pintype "passive"))
      (node (ref "U3") (pin "1") (pinfunction "VCC_1") (pintype "passive"))
    )
    (net (code "53") (name "Net-(U6-VCP)") (class "Default")
      (node (ref "C24") (pin "2") (pinfunction "2_2") (pintype "passive"))
      (node (ref "U6") (pin "11") (pinfunction "VCP_11") (pintype "passive"))
    )
    (net (code "54") (name "Net-(U6-VINT)") (class "Default")
      (node (ref "C25") (pin "1") (pinfunction "1_1") (pintype "passive"))
      (node (ref "U6") (pin "14") (pinfunction "VINT_14") (pintype "passive"))
    )
    (net (code "55") (name "USB_DETECT") (class "Default")
      (node (ref "R7") (pin "1") (pinfunction "1_1") (pintype "passive"))
      (node (ref "R8") (pin "2") (pinfunction "2_2") (pintype "passive"))
      (node (ref "U1") (pin "35") (pinfunction "PA5/PGMRDY_35") (pintype "bidirectional"))
      (node (ref "USB_DETECT_TP") (pin "1") (pinfunction "1_1") (pintype "passive"))
    )
    (net (code "56") (name "VBUS") (class "Default")
      (node (ref "H3") (pin "1") (pinfunction "VBUS_1") (pintype "power_in"))
      (node (ref "R7") (pin "2") (pinfunction "2_2") (pintype "passive"))
      (node (ref "VBUS_TP") (pin "1") (pinfunction "1_1") (pintype "passive"))
    )
    (net (code "57") (name "V_BAT") (class "Default")
      (node (ref "C23") (pin "1") (pinfunction "1_1") (pintype "passive"))
      (node (ref "C24") (pin "1") (pinfunction "1_1") (pintype "passive"))
      (node (ref "C3") (pin "2") (pinfunction "2_2") (pintype "passive"))
      (node (ref "Q1") (pin "2") (pinfunction "2_2") (pintype "passive"))
      (node (ref "R14") (pin "2") (pinfunction "2_2") (pintype "passive"))
      (node (ref "R3") (pin "2") (pinfunction "2_2") (pintype "passive"))
      (node (ref "U2") (pin "2") (pinfunction "VIN_2") (pintype "input"))
      (node (ref "U2") (pin "3") (pinfunction "EN_3") (pintype "output"))
      (node (ref "U6") (pin "12") (pinfunction "VM_12") (pintype "passive"))
      (node (ref "V_BATT_TP") (pin "1") (pinfunction "1_1") (pintype "passive"))
    )
    (net (code "58") (name "unconnected-(H2-Pad3)") (class "Default")
      (node (ref "H2") (pin "3") (pinfunction "3_3") (pintype "passive+no_connect"))
    )
    (net (code "59") (name "unconnected-(H2-Pad9)") (class "Default")
      (node (ref "H2") (pin "9") (pinfunction "9_9") (pintype "passive+no_connect"))
    )
    (net (code "60") (name "unconnected-(H2-Pad10)") (class "Default")
      (node (ref "H2") (pin "10") (pinfunction "10_10") (pintype "passive+no_connect"))
    )
    (net (code "61") (name "unconnected-(H3-ID-Pad4)") (class "Default")
      (node (ref "H3") (pin "4") (pinfunction "ID_4") (pintype "power_in"))
    )
    (net (code "62") (name "unconnected-(H5-Pad2)") (class "Default")
      (node (ref "H5") (pin "2") (pinfunction "2_2") (pintype "passive"))
    )
    (net (code "63") (name "unconnected-(H10-Pad3)") (class "Default")
      (node (ref "H10") (pin "3") (pinfunction "3_3") (pintype "passive+no_connect"))
    )
    (net (code "64") (name "unconnected-(H10-Pad8)") (class "Default")
      (node (ref "H10") (pin "8") (pinfunction "8_8") (pintype "passive+no_connect"))
    )
    (net (code "65") (name "unconnected-(U1A-JTAGSEL-Pad50)") (class "Default")
      (node (ref "U1") (pin "50") (pinfunction "JTAGSEL_50") (pintype "input+no_connect"))
    )
    (net (code "66") (name "unconnected-(U1A-PA6{slash}PGMNOE-Pad34)") (class "Default")
      (node (ref "U1") (pin "34") (pinfunction "PA6/PGMNOE_34") (pintype "bidirectional"))
    )
    (net (code "67") (name "unconnected-(U1A-PA7{slash}XIN32{slash}PGMNVALID-Pad32)") (class "Default")
      (node (ref "U1") (pin "32") (pinfunction "PA7/XIN32/PGMNVALID_32") (pintype "bidirectional+no_connect"))
    )
    (net (code "68") (name "unconnected-(U1A-PA8{slash}XOUT32{slash}PGMM0-Pad31)") (class "Default")
      (node (ref "U1") (pin "31") (pinfunction "PA8/XOUT32/PGMM0_31") (pintype "bidirectional+no_connect"))
    )
    (net (code "69") (name "unconnected-(U1A-PA10{slash}PGMM2-Pad29)") (class "Default")
      (node (ref "U1") (pin "29") (pinfunction "PA10/PGMM2_29") (pintype "bidirectional+no_connect"))
    )
    (net (code "70") (name "unconnected-(U1A-PA16{slash}PGMD4-Pad19)") (class "Default")
      (node (ref "U1") (pin "19") (pinfunction "PA16/PGMD4_19") (pintype "bidirectional+no_connect"))
    )
    (net (code "71") (name "unconnected-(U1A-PA21{slash}PGMD9{slash}AD8-Pad11)") (class "Default")
      (node (ref "U1") (pin "11") (pinfunction "PA21/PGMD9/AD8_11") (pintype "bidirectional+no_connect"))
    )
    (net (code "72") (name "unconnected-(U1A-PA22{slash}PGMD10{slash}AD9-Pad14)") (class "Default")
      (node (ref "U1") (pin "14") (pinfunction "PA22/PGMD10/AD9_14") (pintype "bidirectional+no_connect"))
    )
    (net (code "73") (name "unconnected-(U1A-PA23{slash}PGMD11-Pad15)") (class "Default")
      (node (ref "U1") (pin "15") (pinfunction "PA23/PGMD11_15") (pintype "bidirectional+no_connect"))
    )
    (net (code "74") (name "unconnected-(U1A-PA24{slash}PGMD12-Pad23)") (class "Default")
      (node (ref "U1") (pin "23") (pinfunction "PA24/PGMD12_23") (pintype "bidirectional+no_connect"))
    )
    (net (code "75") (name "unconnected-(U1A-PB1{slash}AD5-Pad4)") (class "Default")
      (node (ref "U1") (pin "4") (pinfunction "PB1/AD5_4") (pintype "bidirectional+no_connect"))
    )
    (net (code "76") (name "unconnected-(U1A-PB2{slash}AD6-Pad5)") (class "Default")
      (node (ref "U1") (pin "5") (pinfunction "PB2/AD6_5") (pintype "bidirectional+no_connect"))
    )
    (net (code "77") (name "unconnected-(U1A-PB3{slash}AD7-Pad6)") (class "Default")
      (node (ref "U1") (pin "6") (pinfunction "PB3/AD7_6") (pintype "bidirectional+no_connect"))
    )
    (net (code "78") (name "unconnected-(U1A-PB13{slash}DAC0-Pad59)") (class "Default")
      (node (ref "U1") (pin "59") (pinfunction "PB13/DAC0_59") (pintype "bidirectional+no_connect"))
    )
    (net (code "79") (name "unconnected-(U1A-PB14{slash}DAC1-Pad63)") (class "Default")
      (node (ref "U1") (pin "63") (pinfunction "PB14/DAC1_63") (pintype "bidirectional+no_connect"))
    )
    (net (code "80") (name "unconnected-(U1A-TDI{slash}PB4-Pad33)") (class "Default")
      (node (ref "U1") (pin "33") (pinfunction "TDI/PB4_33") (pintype "bidirectional+no_connect"))
    )
    (net (code "81") (name "unconnected-(U1A-TDO{slash}TRACESWO{slash}PB5-Pad49)") (class "Default")
      (node (ref "U1") (pin "49") (pinfunction "TDO/TRACESWO/PB5_49") (pintype "bidirectional+no_connect"))
    )
    (net (code "82") (name "unconnected-(U1A-TST-Pad40)") (class "Default")
      (node (ref "U1") (pin "40") (pinfunction "TST_40") (pintype "input+no_connect"))
    )
    (net (code "83") (name "unconnected-(U2-NC-Pad6)") (class "Default")
      (node (ref "U2") (pin "6") (pinfunction "NC_6") (pintype "passive+no_connect"))
    )
    (net (code "84") (name "unconnected-(U4-BYP-Pad4)") (class "Default")
      (node (ref "U4") (pin "4") (pinfunction "BYP_4") (pintype "passive"))
    )
    (net (code "85") (name "unconnected-(U5-BYP-Pad4)") (class "Default")
      (node (ref "U5") (pin "4") (pinfunction "BYP_4") (pintype "passive"))
    )
  )
)
